# EnergyHarvester.net
KiCad netlist of a schematic drawn in Altium Designer
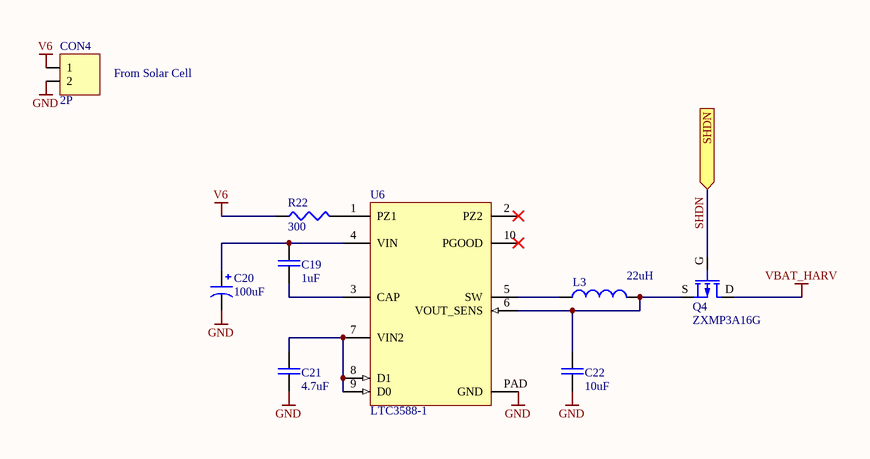
[diagram p0: EnergyHarvester.SchDoc]

(export (version "E")
  (design (tool "Eeschema 10.0.6"))
  (components
    (comp (ref "C19")
      (value "1uF")
      (footprint "0805")
      (description "Capacitor")
      (fields (field (name "OWNER") "Nuno Brum"))
      (libsource (lib "Alcetronics_Devices") (part "CAP"))
    )
    (comp (ref "C20")
      (value "100uF")
      (footprint "RADIAL-5MM")
      (description "Polarized Capacitor")
      (fields (field (name "OWNER") "Nuno Brum"))
      (libsource (lib "Alcetronics_Devices") (part "CAP POL"))
    )
    (comp (ref "C21")
      (value "4.7uF")
      (footprint "0805")
      (description "Capacitor")
      (fields (field (name "OWNER") "Nuno Brum"))
      (libsource (lib "Alcetronics_Devices") (part "CAP"))
    )
    (comp (ref "C22")
      (value "10uF")
      (footprint "0805")
      (description "Capacitor")
      (fields (field (name "OWNER") "Nuno Brum"))
      (libsource (lib "Alcetronics_Devices") (part "CAP"))
    )
    (comp (ref "CON4")
      (value "2P")
      (footprint "INTERLOCK2-5MM-FIXED")
      (description "Connector 2 pins")
      (fields (field (name "OWNER") "Rui Rebelo"))
      (libsource (lib "Alcetronics_EM") (part "CON02"))
    )
    (comp (ref "L3")
      (value "22uH")
      (footprint "7X7")
      (description "Inductor")
      (fields (field (name "OWNER") "Nuno Brum"))
      (libsource (lib "Alcetronics_Devices") (part "IND"))
    )
    (comp (ref "Q4")
      (value "ZXMP3A16G")
      (footprint "SOT-223@GDSD")
      (description "P-Channel Logic Level Enhancement Mode Field Effect Transistor")
      (fields (field (name "OWNER") "Nuno Brum"))
      (libsource (lib "Alcetronics_Devices") (part "MOSFET-P"))
    )
    (comp (ref "R22")
      (value "300")
      (footprint "0805")
      (description "Resistor")
      (fields (field (name "OWNER") "Nuno Brum"))
      (libsource (lib "Alcetronics_Devices") (part "RES"))
    )
    (comp (ref "U6")
      (value "LTC3588-1")
      (footprint "MSOP10@EP")
      (description "Energy harvester")
      (libsource (lib "Alcetronics_IC") (part "LTC3588-1"))
    )
  )
  (nets
    (net (code "1") (name "/SHDN") (class "Default")
      (node (ref "Q4") (pin "G") (pinfunction "G_G") (pintype "passive"))
    )
    (net (code "2") (name "GND") (class "Default")
      (node (ref "C20") (pin "2") (pinfunction "N_2") (pintype "passive"))
      (node (ref "C21") (pin "1") (pinfunction "1_1") (pintype "passive"))
      (node (ref "C22") (pin "1") (pinfunction "1_1") (pintype "passive"))
      (node (ref "CON4") (pin "2") (pinfunction "2_2") (pintype "passive"))
      (node (ref "U6") (pin "PAD") (pinfunction "GND_PAD") (pintype "passive"))
    )
    (net (code "3") (name "Net-(C20-P)") (class "Default")
      (node (ref "C19") (pin "2") (pinfunction "2_2") (pintype "passive"))
      (node (ref "C20") (pin "1") (pinfunction "P_1") (pintype "passive"))
      (node (ref "U6") (pin "4") (pinfunction "VIN_4") (pintype "passive"))
    )
    (net (code "4") (name "Net-(U6-CAP)") (class "Default")
      (node (ref "C19") (pin "1") (pinfunction "1_1") (pintype "passive"))
      (node (ref "U6") (pin "3") (pinfunction "CAP_3") (pintype "passive"))
    )
    (net (code "5") (name "Net-(U6-D0)") (class "Default")
      (node (ref "C21") (pin "2") (pinfunction "2_2") (pintype "passive"))
      (node (ref "U6") (pin "7") (pinfunction "VIN2_7") (pintype "passive"))
      (node (ref "U6") (pin "8") (pinfunction "D1_8") (pintype "input"))
      (node (ref "U6") (pin "9") (pinfunction "D0_9") (pintype "input"))
    )
    (net (code "6") (name "Net-(U6-PZ1)") (class "Default")
      (node (ref "R22") (pin "2") (pinfunction "2_2") (pintype "passive"))
      (node (ref "U6") (pin "1") (pinfunction "PZ1_1") (pintype "passive"))
    )
    (net (code "7") (name "Net-(U6-SW)") (class "Default")
      (node (ref "L3") (pin "1") (pinfunction "1_1") (pintype "passive"))
      (node (ref "U6") (pin "5") (pinfunction "SW_5") (pintype "power_in"))
    )
    (net (code "8") (name "Net-(U6-VOUT_SENS)") (class "Default")
      (node (ref "C22") (pin "2") (pinfunction "2_2") (pintype "passive"))
      (node (ref "L3") (pin "2") (pinfunction "2_2") (pintype "passive"))
      (node (ref "Q4") (pin "S") (pinfunction "S_S") (pintype "passive"))
      (node (ref "U6") (pin "6") (pinfunction "VOUT_SENS_6") (pintype "input"))
    )
    (net (code "9") (name "V6") (class "Default")
      (node (ref "CON4") (pin "1") (pinfunction "1_1") (pintype "passive"))
      (node (ref "R22") (pin "1") (pinfunction "1_1") (pintype "passive"))
    )
    (net (code "10") (name "VBAT_HARV") (class "Default")
      (node (ref "Q4") (pin "D") (pinfunction "D_D") (pintype "passive"))
    )
    (net (code "11") (name "unconnected-(U6-PGOOD-Pad10)") (class "Default")
      (node (ref "U6") (pin "10") (pinfunction "PGOOD_10") (pintype "passive+no_connect"))
    )
    (net (code "12") (name "unconnected-(U6-PZ2-Pad2)") (class "Default")
      (node (ref "U6") (pin "2") (pinfunction "PZ2_2") (pintype "passive+no_connect"))
    )
  )
)
